# Display_LED_Anode_Command.net
KiCad netlist of a schematic drawn in Altium Designer
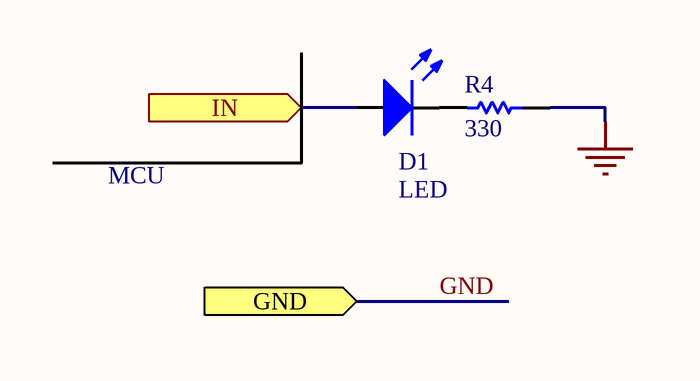
[diagram p0: Display_LED_Anode Command.SchDoc]

(export (version "E")
  (design (tool "Eeschema 10.0.6"))
  (components
    (comp (ref "D1")
      (value "LED")
      (footprint "LED-5mm_Red")
      (description "Typical INFRARED GaAs LED")
      (fields (field (name "MANUFACTURER") "Generic Components") (field (name "PUBLISHER") "Altium Limited"))
      (libsource (lib "Miscellaneous Devices") (part "LED"))
    )
    (comp (ref "R4")
      (value "330")
      (footprint "AXIAL-0.4")
      (description "Resistor")
      (fields
        (field (name "MANUFACTURER") "Generic Components")
        (field (name "Comment") "Res1")
        (field (name "PUBLISHER") "Altium Limited")
      )
      (libsource (lib "Miscellaneous Devices") (part "Res1"))
    )
  )
  (nets
    (net (code "1") (name "/IN") (class "Default")
      (node (ref "D1") (pin "1") (pinfunction "A_1") (pintype "passive"))
    )
    (net (code "2") (name "GND") (class "Default")
      (node (ref "R4") (pin "1") (pinfunction "1_1") (pintype "passive"))
    )
    (net (code "3") (name "Net-(D1-K)") (class "Default")
      (node (ref "D1") (pin "2") (pinfunction "K_2") (pintype "passive"))
      (node (ref "R4") (pin "2") (pinfunction "2_2") (pintype "passive"))
    )
  )
)
